# Stepper.net
KiCad netlist of a schematic drawn in Altium Designer
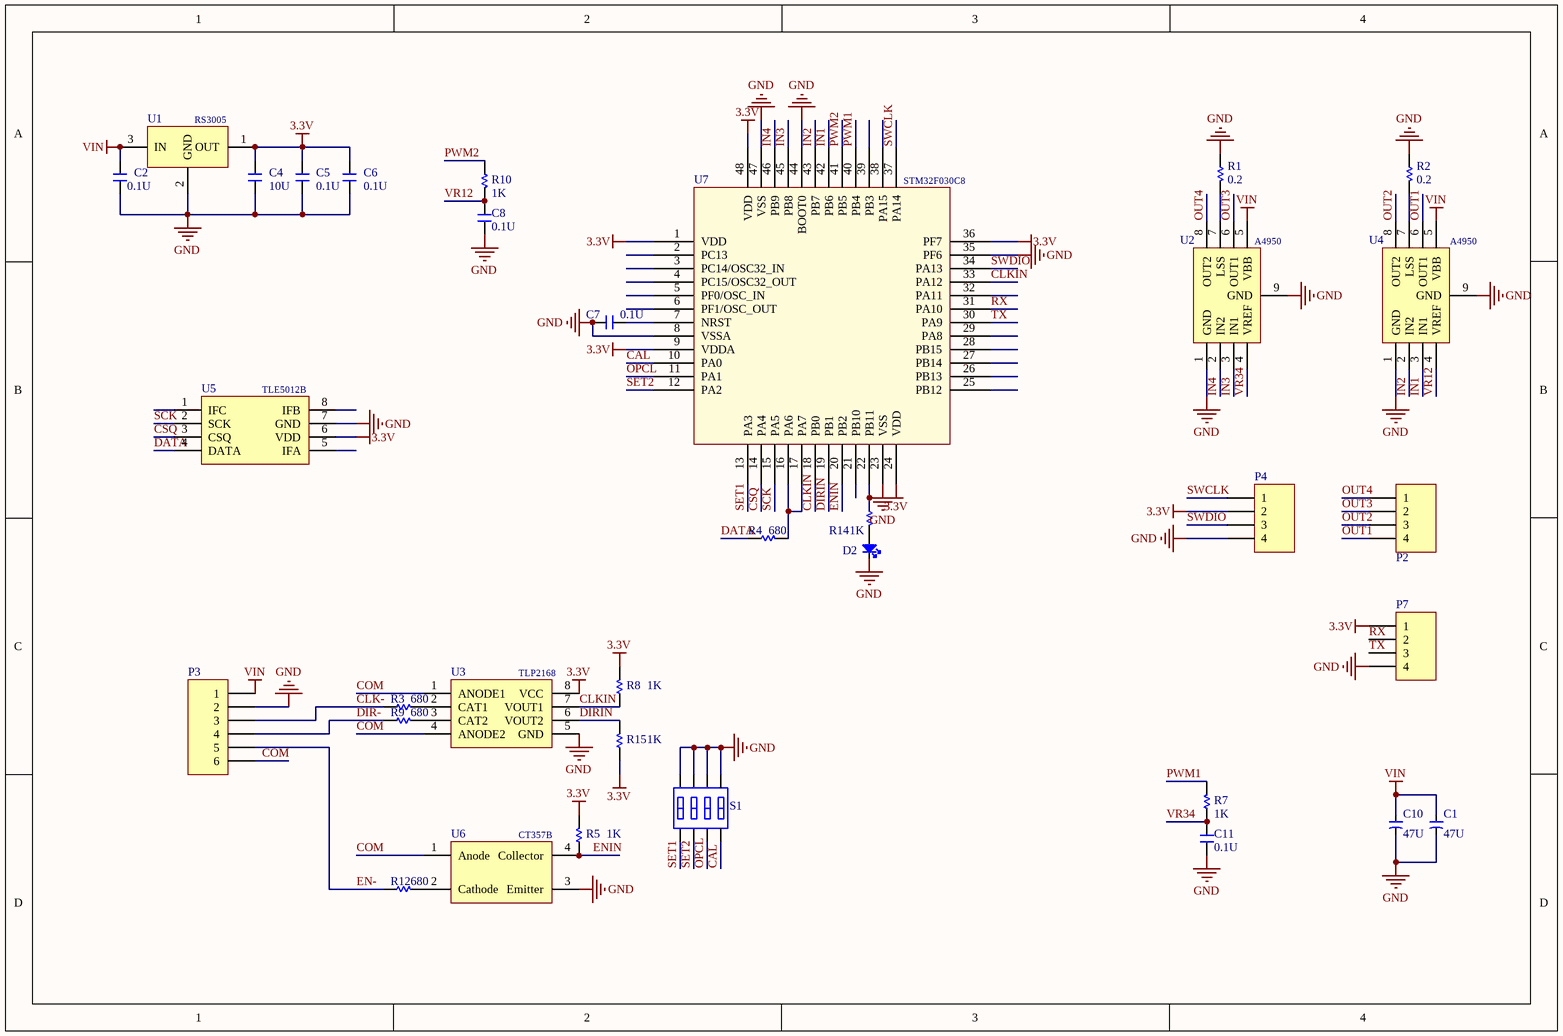
[diagram p0: Stepper.SchDoc]

(export (version "E")
  (design (tool "Eeschema 10.0.6"))
  (components
    (comp (ref "C1")
      (value "47U")
      (footprint "CAP6377")
      (description "Polarized Capacitor (Axial)")
      (fields (field (name "Comment") "CAP POL") (field (name "PUBLISHER") "Altium Limited"))
      (libsource (lib "MySchib") (part "CAP POL"))
    )
    (comp (ref "C2")
      (value "0.1U")
      (footprint "0805")
      (description "Capacitor")
      (fields (field (name "Comment") "CAP") (field (name "PUBLISHER") "Altium Limited"))
      (libsource (lib "MySchib") (part "CAP"))
    )
    (comp (ref "C4")
      (value "10U")
      (footprint "0805")
      (description "Capacitor")
      (fields (field (name "Comment") "CAP") (field (name "PUBLISHER") "Altium Limited"))
      (libsource (lib "MySchib") (part "CAP"))
    )
    (comp (ref "C5")
      (value "0.1U")
      (footprint "0805")
      (description "Capacitor")
      (fields (field (name "Comment") "CAP") (field (name "PUBLISHER") "Altium Limited"))
      (libsource (lib "MySchib") (part "CAP"))
    )
    (comp (ref "C6")
      (value "0.1U")
      (footprint "0805")
      (description "Capacitor")
      (fields (field (name "Comment") "CAP") (field (name "PUBLISHER") "Altium Limited"))
      (libsource (lib "MySchib") (part "CAP"))
    )
    (comp (ref "C7")
      (value "0.1U")
      (footprint "0805")
      (description "Capacitor")
      (fields (field (name "Comment") "CAP") (field (name "PUBLISHER") "Altium Limited"))
      (libsource (lib "MySchib") (part "CAP"))
    )
    (comp (ref "C8")
      (value "0.1U")
      (footprint "0805")
      (description "Capacitor")
      (fields (field (name "Comment") "CAP") (field (name "PUBLISHER") "Altium Limited"))
      (libsource (lib "MySchib") (part "CAP"))
    )
    (comp (ref "C10")
      (value "47U")
      (footprint "CAP6377")
      (description "Polarized Capacitor (Axial)")
      (fields (field (name "Comment") "CAP POL") (field (name "PUBLISHER") "Altium Limited"))
      (libsource (lib "MySchib") (part "CAP POL"))
    )
    (comp (ref "C11")
      (value "0.1U")
      (footprint "0805")
      (description "Capacitor")
      (fields (field (name "Comment") "CAP") (field (name "PUBLISHER") "Altium Limited"))
      (libsource (lib "MySchib") (part "CAP"))
    )
    (comp (ref "D2")
      (value "LED")
      (footprint "0805")
      (description "Typical INFRARED GaAs LED")
      (fields (field (name "PUBLISHER") "Altium Limited"))
      (libsource (lib "MySchib") (part "LED"))
    )
    (comp (ref "P2")
      (value "HEADER4")
      (footprint "4P-2.54MM - S")
      (description "Header, 4-Pin")
      (fields (field (name "PUBLISHER") "Altium Limited"))
      (libsource (lib "MySchib") (part "HEADER4"))
    )
    (comp (ref "P3")
      (value "HEADER6")
      (footprint "XH-6-S")
      (description "Header, 6-Pin")
      (fields (field (name "PUBLISHER") "Altium Limited"))
      (libsource (lib "MySchib") (part "HEADER6"))
    )
    (comp (ref "P4")
      (value "HEADER4")
      (footprint "4P-1.27MM")
      (description "Header, 4-Pin")
      (fields (field (name "PUBLISHER") "Altium Limited"))
      (libsource (lib "MySchib") (part "HEADER4"))
    )
    (comp (ref "P7")
      (value "HEADER4")
      (footprint "4P-1.27MM")
      (description "Header, 4-Pin")
      (fields (field (name "PUBLISHER") "Altium Limited"))
      (libsource (lib "MySchib") (part "HEADER4"))
    )
    (comp (ref "R1")
      (value "0.2")
      (footprint "1206")
      (description "Resistor")
      (fields (field (name "Comment") "RES") (field (name "PUBLISHER") "Altium Limited"))
      (libsource (lib "MySchib") (part "RES"))
    )
    (comp (ref "R2")
      (value "0.2")
      (footprint "1206")
      (description "Resistor")
      (fields (field (name "Comment") "RES") (field (name "PUBLISHER") "Altium Limited"))
      (libsource (lib "MySchib") (part "RES"))
    )
    (comp (ref "R3")
      (value "680")
      (footprint "0805")
      (description "Resistor")
      (fields (field (name "Comment") "RES") (field (name "PUBLISHER") "Altium Limited"))
      (libsource (lib "MySchib") (part "RES"))
    )
    (comp (ref "R4")
      (value "680")
      (footprint "0805")
      (description "Resistor")
      (fields (field (name "Comment") "RES") (field (name "PUBLISHER") "Altium Limited"))
      (libsource (lib "MySchib") (part "RES"))
    )
    (comp (ref "R5")
      (value "1K")
      (footprint "0805")
      (description "Resistor")
      (fields (field (name "Comment") "RES") (field (name "PUBLISHER") "Altium Limited"))
      (libsource (lib "MySchib") (part "RES"))
    )
    (comp (ref "R7")
      (value "1K")
      (footprint "0805")
      (description "Resistor")
      (fields (field (name "Comment") "RES") (field (name "PUBLISHER") "Altium Limited"))
      (libsource (lib "MySchib") (part "RES"))
    )
    (comp (ref "R8")
      (value "1K")
      (footprint "0805")
      (description "Resistor")
      (fields (field (name "Comment") "RES") (field (name "PUBLISHER") "Altium Limited"))
      (libsource (lib "MySchib") (part "RES"))
    )
    (comp (ref "R9")
      (value "680")
      (footprint "0805")
      (description "Resistor")
      (fields (field (name "Comment") "RES") (field (name "PUBLISHER") "Altium Limited"))
      (libsource (lib "MySchib") (part "RES"))
    )
    (comp (ref "R10")
      (value "1K")
      (footprint "0805")
      (description "Resistor")
      (fields (field (name "Comment") "RES") (field (name "PUBLISHER") "Altium Limited"))
      (libsource (lib "MySchib") (part "RES"))
    )
    (comp (ref "R12")
      (value "680")
      (footprint "0805")
      (description "Resistor")
      (fields (field (name "Comment") "RES") (field (name "PUBLISHER") "Altium Limited"))
      (libsource (lib "MySchib") (part "RES"))
    )
    (comp (ref "R14")
      (value "1K")
      (footprint "0805")
      (description "Resistor")
      (fields (field (name "Comment") "RES") (field (name "PUBLISHER") "Altium Limited"))
      (libsource (lib "MySchib") (part "RES"))
    )
    (comp (ref "R15")
      (value "1K")
      (footprint "0805")
      (description "Resistor")
      (fields (field (name "Comment") "RES") (field (name "PUBLISHER") "Altium Limited"))
      (libsource (lib "MySchib") (part "RES"))
    )
    (comp (ref "S1")
      (value "SWDIP-4")
      (footprint "SWSUR-4")
      (description "DIP Switch, 4Position, SPST")
      (fields (field (name "PUBLISHER") "Altium Limited"))
      (libsource (lib "MySchib") (part "SWDIP-4"))
    )
    (comp (ref "U1")
      (value "RS3005")
      (footprint "SOT89")
      (description "Positive Voltage Regulator")
      (fields (field (name "PUBLISHER") "Altium Limited"))
      (libsource (lib "MySchib") (part "RS3005"))
    )
    (comp (ref "U2")
      (value "A4950")
      (footprint "SOIC-8_A4950")
      (description "Dual Full-Bridge  DMOS PWM Motor Driver")
      (libsource (lib "MySchib") (part "A4950"))
    )
    (comp (ref "U3")
      (value "TLP2168")
      (footprint "SO-8_3.9mm")
      (description "HIGH SPEED 10MBit/s LOGIC GATE  PHOTOCOUPLER")
      (libsource (lib "MySchib") (part "TLP2168"))
    )
    (comp (ref "U4")
      (value "A4950")
      (footprint "SOIC-8_A4950")
      (description "Dual Full-Bridge  DMOS PWM Motor Driver")
      (libsource (lib "MySchib") (part "A4950"))
    )
    (comp (ref "U5")
      (value "TLE5012B")
      (footprint "PG-DSO-8F")
      (description "GMR-Based Angle Sensor")
      (libsource (lib "MySchib") (part "TLE5012B"))
    )
    (comp (ref "U6")
      (value "CT357B")
      (footprint "SOP-4_P2.54")
      (description "4 PIN PHOTOTRANSISTOR")
      (libsource (lib "MySchib") (part "EL817"))
    )
    (comp (ref "U7")
      (value "STM32F030C8")
      (footprint "LQFP-48_7x7x05P")
      (description "ST Microcontroller")
      (libsource (lib "MySchib") (part "STM32F030C8"))
    )
  )
  (nets
    (net (code "1") (name "/CAL") (class "Default")
      (node (ref "S1") (pin "7") (pinfunction "A4_7") (pintype "passive"))
      (node (ref "U7") (pin "10") (pinfunction "PA0_10") (pintype "passive"))
    )
    (net (code "2") (name "/CLK-") (class "Default")
      (node (ref "P3") (pin "3") (pinfunction "3_3") (pintype "passive"))
      (node (ref "R3") (pin "1") (pinfunction "1_1") (pintype "passive"))
    )
    (net (code "3") (name "/CLKIN") (class "Default")
      (node (ref "R8") (pin "1") (pinfunction "1_1") (pintype "passive"))
      (node (ref "U3") (pin "7") (pinfunction "VOUT1_7") (pintype "passive"))
      (node (ref "U7") (pin "18") (pinfunction "PB0_18") (pintype "passive"))
      (node (ref "U7") (pin "33") (pinfunction "PA12_33") (pintype "passive"))
    )
    (net (code "4") (name "/COM") (class "Default")
      (node (ref "P3") (pin "6") (pinfunction "6_6") (pintype "passive"))
      (node (ref "U3") (pin "1") (pinfunction "ANODE1_1") (pintype "passive"))
      (node (ref "U3") (pin "4") (pinfunction "ANODE2_4") (pintype "passive"))
      (node (ref "U6") (pin "1") (pinfunction "Anode_1") (pintype "passive"))
    )
    (net (code "5") (name "/CSQ") (class "Default")
      (node (ref "U5") (pin "3") (pinfunction "CSQ_3") (pintype "passive"))
      (node (ref "U7") (pin "14") (pinfunction "PA4_14") (pintype "passive"))
    )
    (net (code "6") (name "/DATA") (class "Default")
      (node (ref "R4") (pin "1") (pinfunction "1_1") (pintype "passive"))
      (node (ref "U5") (pin "4") (pinfunction "DATA_4") (pintype "passive"))
    )
    (net (code "7") (name "/DIR-") (class "Default")
      (node (ref "P3") (pin "4") (pinfunction "4_4") (pintype "passive"))
      (node (ref "R9") (pin "1") (pinfunction "1_1") (pintype "passive"))
    )
    (net (code "8") (name "/DIRIN") (class "Default")
      (node (ref "R15") (pin "2") (pinfunction "2_2") (pintype "passive"))
      (node (ref "U3") (pin "6") (pinfunction "VOUT2_6") (pintype "passive"))
      (node (ref "U7") (pin "19") (pinfunction "PB1_19") (pintype "passive"))
    )
    (net (code "9") (name "/EN-") (class "Default")
      (node (ref "P3") (pin "5") (pinfunction "5_5") (pintype "passive"))
      (node (ref "R12") (pin "1") (pinfunction "1_1") (pintype "passive"))
    )
    (net (code "10") (name "/ENIN") (class "Default")
      (node (ref "R5") (pin "1") (pinfunction "1_1") (pintype "passive"))
      (node (ref "U6") (pin "4") (pinfunction "Collector_4") (pintype "passive"))
      (node (ref "U7") (pin "20") (pinfunction "PB2_20") (pintype "passive"))
    )
    (net (code "11") (name "/IN1") (class "Default")
      (node (ref "U4") (pin "3") (pinfunction "IN1_3") (pintype "passive"))
      (node (ref "U7") (pin "42") (pinfunction "PB6_42") (pintype "passive"))
    )
    (net (code "12") (name "/IN2") (class "Default")
      (node (ref "U4") (pin "2") (pinfunction "IN2_2") (pintype "passive"))
      (node (ref "U7") (pin "43") (pinfunction "PB7_43") (pintype "passive"))
    )
    (net (code "13") (name "/IN3") (class "Default")
      (node (ref "U2") (pin "3") (pinfunction "IN1_3") (pintype "passive"))
      (node (ref "U7") (pin "45") (pinfunction "PB8_45") (pintype "passive"))
    )
    (net (code "14") (name "/IN4") (class "Default")
      (node (ref "U2") (pin "2") (pinfunction "IN2_2") (pintype "passive"))
      (node (ref "U7") (pin "46") (pinfunction "PB9_46") (pintype "passive"))
    )
    (net (code "15") (name "/OPCL") (class "Default")
      (node (ref "S1") (pin "5") (pinfunction "A3_5") (pintype "passive"))
      (node (ref "U7") (pin "11") (pinfunction "PA1_11") (pintype "passive"))
    )
    (net (code "16") (name "/OUT1") (class "Default")
      (node (ref "P2") (pin "4") (pinfunction "4_4") (pintype "passive"))
      (node (ref "U4") (pin "6") (pinfunction "OUT1_6") (pintype "passive"))
    )
    (net (code "17") (name "/OUT2") (class "Default")
      (node (ref "P2") (pin "3") (pinfunction "3_3") (pintype "passive"))
      (node (ref "U4") (pin "8") (pinfunction "OUT2_8") (pintype "passive"))
    )
    (net (code "18") (name "/OUT3") (class "Default")
      (node (ref "P2") (pin "2") (pinfunction "2_2") (pintype "passive"))
      (node (ref "U2") (pin "6") (pinfunction "OUT1_6") (pintype "passive"))
    )
    (net (code "19") (name "/OUT4") (class "Default")
      (node (ref "P2") (pin "1") (pinfunction "1_1") (pintype "passive"))
      (node (ref "U2") (pin "8") (pinfunction "OUT2_8") (pintype "passive"))
    )
    (net (code "20") (name "/PWM1") (class "Default")
      (node (ref "R7") (pin "2") (pinfunction "2_2") (pintype "passive"))
      (node (ref "U7") (pin "40") (pinfunction "PB4_40") (pintype "passive"))
    )
    (net (code "21") (name "/PWM2") (class "Default")
      (node (ref "R10") (pin "1") (pinfunction "1_1") (pintype "passive"))
      (node (ref "U7") (pin "41") (pinfunction "PB5_41") (pintype "passive"))
    )
    (net (code "22") (name "/RX") (class "Default")
      (node (ref "P7") (pin "2") (pinfunction "2_2") (pintype "passive"))
      (node (ref "U7") (pin "31") (pinfunction "PA10_31") (pintype "passive"))
    )
    (net (code "23") (name "/SCK") (class "Default")
      (node (ref "U5") (pin "2") (pinfunction "SCK_2") (pintype "passive"))
      (node (ref "U7") (pin "15") (pinfunction "PA5_15") (pintype "passive"))
    )
    (net (code "24") (name "/SET1") (class "Default")
      (node (ref "S1") (pin "1") (pinfunction "A1_1") (pintype "passive"))
      (node (ref "U7") (pin "13") (pinfunction "PA3_13") (pintype "passive"))
    )
    (net (code "25") (name "/SET2") (class "Default")
      (node (ref "S1") (pin "3") (pinfunction "A2_3") (pintype "passive"))
      (node (ref "U7") (pin "12") (pinfunction "PA2_12") (pintype "passive"))
    )
    (net (code "26") (name "/SWCLK") (class "Default")
      (node (ref "P4") (pin "1") (pinfunction "1_1") (pintype "passive"))
      (node (ref "U7") (pin "37") (pinfunction "PA14_37") (pintype "passive"))
    )
    (net (code "27") (name "/SWDIO") (class "Default")
      (node (ref "P4") (pin "3") (pinfunction "3_3") (pintype "passive"))
      (node (ref "U7") (pin "34") (pinfunction "PA13_34") (pintype "passive"))
    )
    (net (code "28") (name "/TX") (class "Default")
      (node (ref "P7") (pin "3") (pinfunction "3_3") (pintype "passive"))
      (node (ref "U7") (pin "30") (pinfunction "PA9_30") (pintype "passive"))
    )
    (net (code "29") (name "/VR12") (class "Default")
      (node (ref "C8") (pin "1") (pinfunction "1_1") (pintype "passive"))
      (node (ref "R10") (pin "2") (pinfunction "2_2") (pintype "passive"))
      (node (ref "U4") (pin "4") (pinfunction "VREF_4") (pintype "passive"))
    )
    (net (code "30") (name "/VR34") (class "Default")
      (node (ref "C11") (pin "1") (pinfunction "1_1") (pintype "passive"))
      (node (ref "R7") (pin "1") (pinfunction "1_1") (pintype "passive"))
      (node (ref "U2") (pin "4") (pinfunction "VREF_4") (pintype "passive"))
    )
    (net (code "31") (name "3.3V") (class "Default")
      (node (ref "C4") (pin "1") (pinfunction "1_1") (pintype "passive"))
      (node (ref "C5") (pin "1") (pinfunction "1_1") (pintype "passive"))
      (node (ref "C6") (pin "1") (pinfunction "1_1") (pintype "passive"))
      (node (ref "P4") (pin "2") (pinfunction "2_2") (pintype "passive"))
      (node (ref "P7") (pin "1") (pinfunction "1_1") (pintype "passive"))
      (node (ref "R15") (pin "1") (pinfunction "1_1") (pintype "passive"))
      (node (ref "R5") (pin "2") (pinfunction "2_2") (pintype "passive"))
      (node (ref "R8") (pin "2") (pinfunction "2_2") (pintype "passive"))
      (node (ref "U1") (pin "1") (pinfunction "OUT_1") (pintype "power_in"))
      (node (ref "U3") (pin "8") (pinfunction "VCC_8") (pintype "passive"))
      (node (ref "U5") (pin "6") (pinfunction "VDD_6") (pintype "passive"))
      (node (ref "U7") (pin "1") (pinfunction "VDD_1") (pintype "passive"))
      (node (ref "U7") (pin "24") (pinfunction "VDD_24") (pintype "passive"))
      (node (ref "U7") (pin "36") (pinfunction "PF7_36") (pintype "passive"))
      (node (ref "U7") (pin "48") (pinfunction "VDD_48") (pintype "passive"))
      (node (ref "U7") (pin "9") (pinfunction "VDDA_9") (pintype "passive"))
    )
    (net (code "32") (name "GND") (class "Default")
      (node (ref "C1") (pin "2") (pinfunction "2_2") (pintype "passive"))
      (node (ref "C10") (pin "2") (pinfunction "2_2") (pintype "passive"))
      (node (ref "C11") (pin "2") (pinfunction "2_2") (pintype "passive"))
      (node (ref "C2") (pin "2") (pinfunction "2_2") (pintype "passive"))
      (node (ref "C4") (pin "2") (pinfunction "2_2") (pintype "passive"))
      (node (ref "C5") (pin "2") (pinfunction "2_2") (pintype "passive"))
      (node (ref "C6") (pin "2") (pinfunction "2_2") (pintype "passive"))
      (node (ref "C7") (pin "1") (pinfunction "1_1") (pintype "passive"))
      (node (ref "C8") (pin "2") (pinfunction "2_2") (pintype "passive"))
      (node (ref "D2") (pin "2") (pinfunction "K_2") (pintype "passive"))
      (node (ref "P3") (pin "2") (pinfunction "2_2") (pintype "passive"))
      (node (ref "P4") (pin "4") (pinfunction "4_4") (pintype "passive"))
      (node (ref "P7") (pin "4") (pinfunction "4_4") (pintype "passive"))
      (node (ref "R1") (pin "1") (pinfunction "1_1") (pintype "passive"))
      (node (ref "R2") (pin "1") (pinfunction "1_1") (pintype "passive"))
      (node (ref "S1") (pin "2") (pinfunction "B1_2") (pintype "passive"))
      (node (ref "S1") (pin "4") (pinfunction "B2_4") (pintype "passive"))
      (node (ref "S1") (pin "6") (pinfunction "B3_6") (pintype "passive"))
      (node (ref "S1") (pin "8") (pinfunction "B4_8") (pintype "passive"))
      (node (ref "U1") (pin "2") (pinfunction "GND_2") (pintype "power_in"))
      (node (ref "U2") (pin "1") (pinfunction "GND_1") (pintype "passive"))
      (node (ref "U2") (pin "9") (pinfunction "GND_9") (pintype "passive"))
      (node (ref "U3") (pin "5") (pinfunction "GND_5") (pintype "passive"))
      (node (ref "U4") (pin "1") (pinfunction "GND_1") (pintype "passive"))
      (node (ref "U4") (pin "9") (pinfunction "GND_9") (pintype "passive"))
      (node (ref "U5") (pin "7") (pinfunction "GND_7") (pintype "passive"))
      (node (ref "U6") (pin "3") (pinfunction "Emitter_3") (pintype "passive"))
      (node (ref "U7") (pin "23") (pinfunction "VSS_23") (pintype "passive"))
      (node (ref "U7") (pin "35") (pinfunction "PF6_35") (pintype "passive"))
      (node (ref "U7") (pin "44") (pinfunction "BOOT0_44") (pintype "passive"))
      (node (ref "U7") (pin "47") (pinfunction "VSS_47") (pintype "passive"))
      (node (ref "U7") (pin "8") (pinfunction "VSSA_8") (pintype "passive"))
    )
    (net (code "33") (name "Net-(D2-A)") (class "Default")
      (node (ref "D2") (pin "1") (pinfunction "A_1") (pintype "passive"))
      (node (ref "R14") (pin "2") (pinfunction "2_2") (pintype "passive"))
    )
    (net (code "34") (name "Net-(U2-LSS)") (class "Default")
      (node (ref "R1") (pin "2") (pinfunction "2_2") (pintype "passive"))
      (node (ref "U2") (pin "7") (pinfunction "LSS_7") (pintype "passive"))
    )
    (net (code "35") (name "Net-(U3-CAT1)") (class "Default")
      (node (ref "R3") (pin "2") (pinfunction "2_2") (pintype "passive"))
      (node (ref "U3") (pin "2") (pinfunction "CAT1_2") (pintype "passive"))
    )
    (net (code "36") (name "Net-(U3-CAT2)") (class "Default")
      (node (ref "R9") (pin "2") (pinfunction "2_2") (pintype "passive"))
      (node (ref "U3") (pin "3") (pinfunction "CAT2_3") (pintype "passive"))
    )
    (net (code "37") (name "Net-(U4-LSS)") (class "Default")
      (node (ref "R2") (pin "2") (pinfunction "2_2") (pintype "passive"))
      (node (ref "U4") (pin "7") (pinfunction "LSS_7") (pintype "passive"))
    )
    (net (code "38") (name "Net-(U6-Cathode)") (class "Default")
      (node (ref "R12") (pin "2") (pinfunction "2_2") (pintype "passive"))
      (node (ref "U6") (pin "2") (pinfunction "Cathode_2") (pintype "passive"))
    )
    (net (code "39") (name "Net-(U7-NRST)") (class "Default")
      (node (ref "C7") (pin "2") (pinfunction "2_2") (pintype "passive"))
      (node (ref "U7") (pin "7") (pinfunction "NRST_7") (pintype "passive"))
    )
    (net (code "40") (name "Net-(U7-PA6)") (class "Default")
      (node (ref "R4") (pin "2") (pinfunction "2_2") (pintype "passive"))
      (node (ref "U7") (pin "16") (pinfunction "PA6_16") (pintype "passive"))
      (node (ref "U7") (pin "17") (pinfunction "PA7_17") (pintype "passive"))
    )
    (net (code "41") (name "Net-(U7-PB11)") (class "Default")
      (node (ref "R14") (pin "1") (pinfunction "1_1") (pintype "passive"))
      (node (ref "U7") (pin "22") (pinfunction "PB11_22") (pintype "passive"))
    )
    (net (code "42") (name "VIN") (class "Default")
      (node (ref "C1") (pin "1") (pinfunction "1_1") (pintype "passive"))
      (node (ref "C10") (pin "1") (pinfunction "1_1") (pintype "passive"))
      (node (ref "C2") (pin "1") (pinfunction "1_1") (pintype "passive"))
      (node (ref "P3") (pin "1") (pinfunction "1_1") (pintype "passive"))
      (node (ref "U1") (pin "3") (pinfunction "IN_3") (pintype "power_in"))
      (node (ref "U2") (pin "5") (pinfunction "VBB_5") (pintype "passive"))
      (node (ref "U4") (pin "5") (pinfunction "VBB_5") (pintype "passive"))
    )
    (net (code "43") (name "unconnected-(U5-IFA-Pad5)") (class "Default")
      (node (ref "U5") (pin "5") (pinfunction "IFA_5") (pintype "passive"))
    )
    (net (code "44") (name "unconnected-(U5-IFB-Pad8)") (class "Default")
      (node (ref "U5") (pin "8") (pinfunction "IFB_8") (pintype "passive"))
    )
    (net (code "45") (name "unconnected-(U5-IFC-Pad1)") (class "Default")
      (node (ref "U5") (pin "1") (pinfunction "IFC_1") (pintype "passive"))
    )
    (net (code "46") (name "unconnected-(U7-PA8-Pad29)") (class "Default")
      (node (ref "U7") (pin "29") (pinfunction "PA8_29") (pintype "passive"))
    )
    (net (code "47") (name "unconnected-(U7-PA11-Pad32)") (class "Default")
      (node (ref "U7") (pin "32") (pinfunction "PA11_32") (pintype "passive"))
    )
    (net (code "48") (name "unconnected-(U7-PA15-Pad38)") (class "Default")
      (node (ref "U7") (pin "38") (pinfunction "PA15_38") (pintype "passive"))
    )
    (net (code "49") (name "unconnected-(U7-PB3-Pad39)") (class "Default")
      (node (ref "U7") (pin "39") (pinfunction "PB3_39") (pintype "passive"))
    )
    (net (code "50") (name "unconnected-(U7-PB10-Pad21)") (class "Default")
      (node (ref "U7") (pin "21") (pinfunction "PB10_21") (pintype "passive"))
    )
    (net (code "51") (name "unconnected-(U7-PB12-Pad25)") (class "Default")
      (node (ref "U7") (pin "25") (pinfunction "PB12_25") (pintype "passive"))
    )
    (net (code "52") (name "unconnected-(U7-PB13-Pad26)") (class "Default")
      (node (ref "U7") (pin "26") (pinfunction "PB13_26") (pintype "passive"))
    )
    (net (code "53") (name "unconnected-(U7-PB14-Pad27)") (class "Default")
      (node (ref "U7") (pin "27") (pinfunction "PB14_27") (pintype "passive"))
    )
    (net (code "54") (name "unconnected-(U7-PB15-Pad28)") (class "Default")
      (node (ref "U7") (pin "28") (pinfunction "PB15_28") (pintype "passive"))
    )
    (net (code "55") (name "unconnected-(U7-PC13-Pad2)") (class "Default")
      (node (ref "U7") (pin "2") (pinfunction "PC13_2") (pintype "passive"))
    )
    (net (code "56") (name "unconnected-(U7-PC14{slash}OSC32_IN-Pad3)") (class "Default")
      (node (ref "U7") (pin "3") (pinfunction "PC14/OSC32_IN_3") (pintype "passive"))
    )
    (net (code "57") (name "unconnected-(U7-PC15{slash}OSC32_OUT-Pad4)") (class "Default")
      (node (ref "U7") (pin "4") (pinfunction "PC15/OSC32_OUT_4") (pintype "power_in"))
    )
    (net (code "58") (name "unconnected-(U7-PF0{slash}OSC_IN-Pad5)") (class "Default")
      (node (ref "U7") (pin "5") (pinfunction "PF0/OSC_IN_5") (pintype "power_in"))
    )
    (net (code "59") (name "unconnected-(U7-PF1{slash}OSC_OUT-Pad6)") (class "Default")
      (node (ref "U7") (pin "6") (pinfunction "PF1/OSC_OUT_6") (pintype "power_in"))
    )
  )
)
